# LM358.net
KiCad netlist of a schematic drawn in Altium Designer
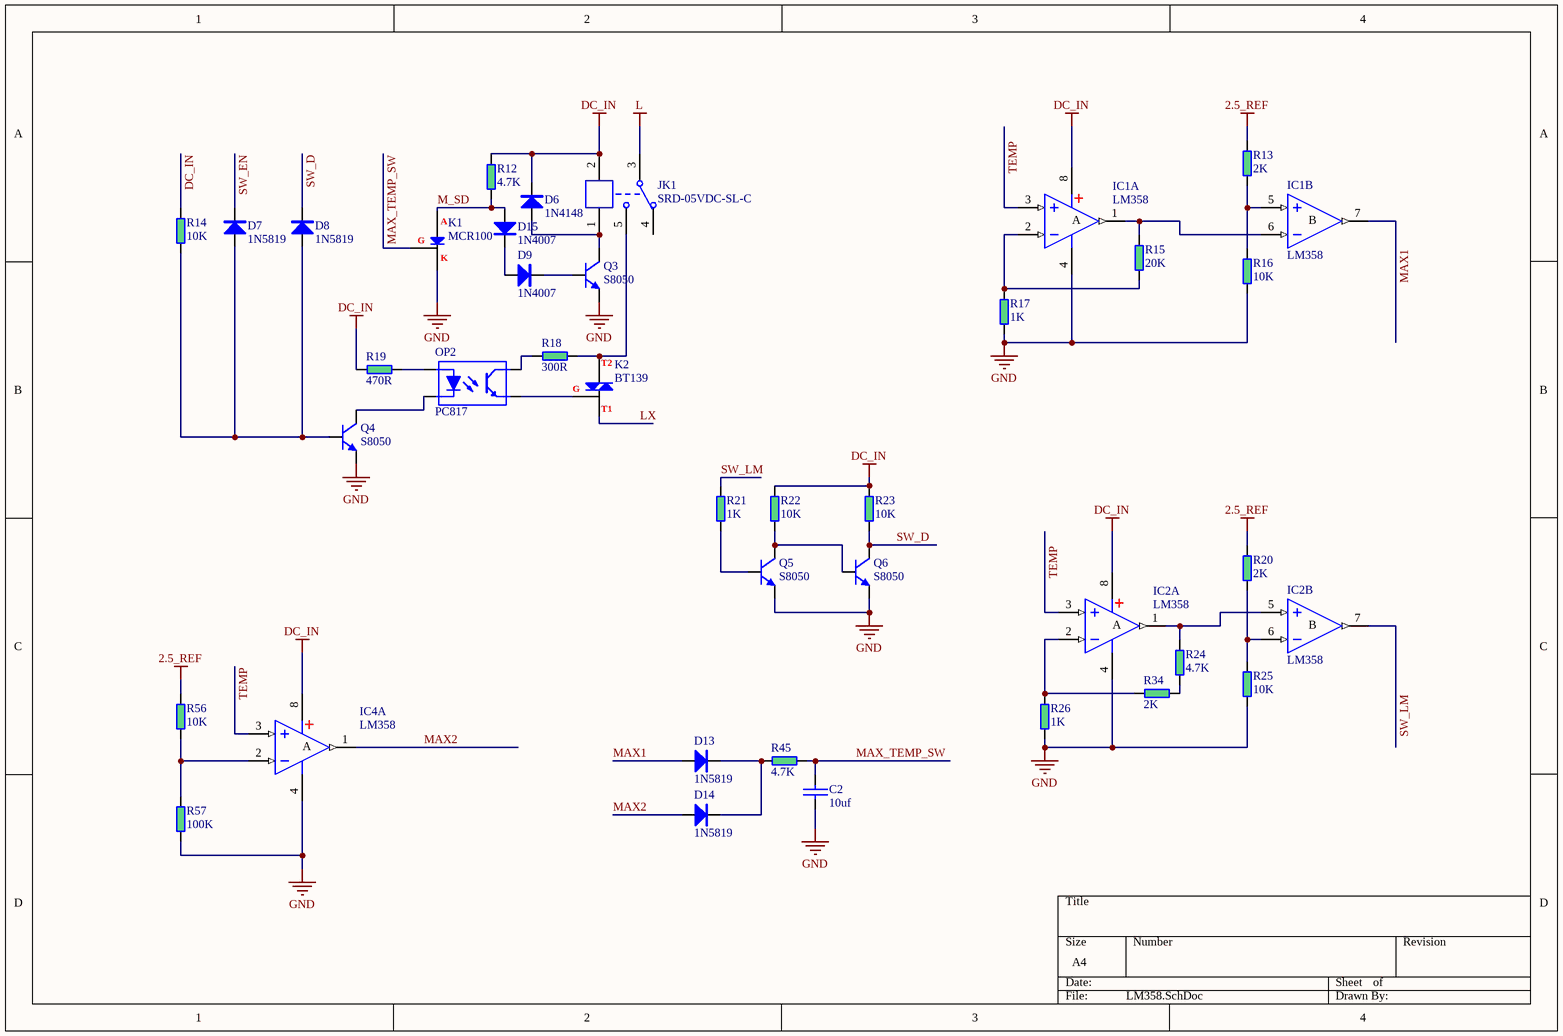
[diagram p0: LM358.SchDoc]

(export (version "E")
  (design (tool "Eeschema 10.0.6"))
  (components
    (comp (ref "C2")
      (value "10uf")
      (footprint "C 0603")
      (description "电容")
      (fields (field (name "Comment") "04.Cap"))
      (libsource (lib "电子元件") (part "04.Cap"))
    )
    (comp (ref "D6")
      (value "1N4148")
      (footprint "D 1N4148-LL34")
      (description "二极管")
      (libsource (lib "电子元件") (part "12.Diode"))
    )
    (comp (ref "D7")
      (value "1N5819")
      (footprint "D 1N5819W-SOD123")
      (description "二极管")
      (libsource (lib "电子元件") (part "12.Diode"))
    )
    (comp (ref "D8")
      (value "1N5819")
      (footprint "D 1N5819W-SOD123")
      (description "二极管")
      (libsource (lib "电子元件") (part "12.Diode"))
    )
    (comp (ref "D9")
      (value "1N4007")
      (footprint "D 1N4007-SOD123")
      (description "二极管")
      (libsource (lib "电子元件") (part "12.Diode"))
    )
    (comp (ref "D13")
      (value "1N5819")
      (footprint "D 1N5819W-SOD123")
      (description "二极管")
      (libsource (lib "电子元件") (part "12.Diode"))
    )
    (comp (ref "D14")
      (value "1N5819")
      (footprint "D 1N5819W-SOD123")
      (description "二极管")
      (libsource (lib "电子元件") (part "12.Diode"))
    )
    (comp (ref "D15")
      (value "1N4007")
      (footprint "D 1N4007-SOD123")
      (description "二极管")
      (libsource (lib "电子元件") (part "12.Diode"))
    )
    (comp (ref "IC1")
      (value "LM358")
      (footprint "SOP8")
      (description "双路运放")
      (fields (field (name "版权归属") "源创客"))
      (libsource (lib "集成IC") (part "LM358"))
    )
    (comp (ref "IC2")
      (value "LM358")
      (footprint "SOP8")
      (description "双路运放")
      (fields (field (name "版权归属") "源创客"))
      (libsource (lib "集成IC") (part "LM358"))
    )
    (comp (ref "IC4")
      (value "LM358")
      (footprint "SOP8")
      (description "双路运放")
      (fields (field (name "版权归属") "源创客"))
      (libsource (lib "集成IC") (part "LM358"))
    )
    (comp (ref "JK1")
      (value "SRD-05VDC-SL-C")
      (footprint "SRD-C_B")
      (description "5V一组转换")
      (fields (field (name "版权归属") "源创客"))
      (libsource (lib "继电器") (part "SRD-05VDC-SL-C"))
    )
    (comp (ref "K1")
      (value "MCR100")
      (footprint "IGBT MCR100-SOT23")
      (description "单向可控硅-晶闸管")
      (libsource (lib "电子元件") (part "20.IGBT"))
    )
    (comp (ref "K2")
      (value "BT139")
      (footprint "IGBT BT139")
      (description "双向可控硅-晶闸管")
      (libsource (lib "电子元件") (part "19.IGBT-Bi"))
    )
    (comp (ref "OP2")
      (value "PC817")
      (footprint "OP MOC3041")
      (description "光耦")
      (libsource (lib "电子元件") (part "17.Optocoupler"))
    )
    (comp (ref "Q3")
      (value "S8050")
      (footprint "BJT-S8050-SOT23")
      (description "三极管 NPN")
      (libsource (lib "电子元件") (part "07.BJT(N)"))
    )
    (comp (ref "Q4")
      (value "S8050")
      (footprint "BJT-S8050-SOT23")
      (description "三极管 NPN")
      (libsource (lib "电子元件") (part "07.BJT(N)"))
    )
    (comp (ref "Q5")
      (value "S8050")
      (footprint "BJT-S8050-SOT23")
      (description "三极管 NPN")
      (libsource (lib "电子元件") (part "07.BJT(N)"))
    )
    (comp (ref "Q6")
      (value "S8050")
      (footprint "BJT-S8050-SOT23")
      (description "三极管 NPN")
      (libsource (lib "电子元件") (part "07.BJT(N)"))
    )
    (comp (ref "R12")
      (value "4.7K")
      (footprint "R 0603")
      (description "电阻")
      (libsource (lib "") (part "01.Res_1"))
    )
    (comp (ref "R13")
      (value "2K")
      (footprint "R 0603")
      (description "电阻")
      (libsource (lib "") (part "01.Res_1"))
    )
    (comp (ref "R14")
      (value "10K")
      (footprint "R 0603")
      (description "电阻")
      (libsource (lib "") (part "01.Res_1"))
    )
    (comp (ref "R15")
      (value "20K")
      (footprint "R 0603")
      (description "电阻")
      (libsource (lib "") (part "01.Res_1"))
    )
    (comp (ref "R16")
      (value "10K")
      (footprint "R 0603")
      (description "电阻")
      (libsource (lib "") (part "01.Res_1"))
    )
    (comp (ref "R17")
      (value "1K")
      (footprint "R 0603")
      (description "电阻")
      (libsource (lib "") (part "01.Res_1"))
    )
    (comp (ref "R18")
      (value "300R")
      (footprint "RS 1/4W-V3")
      (description "电阻")
      (libsource (lib "电子元件") (part "01.Res"))
    )
    (comp (ref "R19")
      (value "470R")
      (footprint "R 0603")
      (description "电阻")
      (libsource (lib "电子元件") (part "01.Res"))
    )
    (comp (ref "R20")
      (value "2K")
      (footprint "R 0603")
      (description "电阻")
      (libsource (lib "") (part "01.Res_1"))
    )
    (comp (ref "R21")
      (value "1K")
      (footprint "R 0603")
      (description "电阻")
      (libsource (lib "") (part "01.Res_1"))
    )
    (comp (ref "R22")
      (value "10K")
      (footprint "R 0603")
      (description "电阻")
      (libsource (lib "") (part "01.Res_1"))
    )
    (comp (ref "R23")
      (value "10K")
      (footprint "R 0603")
      (description "电阻")
      (libsource (lib "") (part "01.Res_1"))
    )
    (comp (ref "R24")
      (value "4.7K")
      (footprint "R 0603")
      (description "电阻")
      (libsource (lib "") (part "01.Res_1"))
    )
    (comp (ref "R25")
      (value "10K")
      (footprint "R 0603")
      (description "电阻")
      (libsource (lib "") (part "01.Res_1"))
    )
    (comp (ref "R26")
      (value "1K")
      (footprint "R 0603")
      (description "电阻")
      (libsource (lib "") (part "01.Res_1"))
    )
    (comp (ref "R34")
      (value "2K")
      (footprint "R 0603")
      (description "电阻")
      (libsource (lib "电子元件") (part "01.Res"))
    )
    (comp (ref "R45")
      (value "4.7K")
      (footprint "R 0603")
      (description "电阻")
      (libsource (lib "电子元件") (part "01.Res"))
    )
    (comp (ref "R56")
      (value "10K")
      (footprint "R 0603")
      (description "电阻")
      (libsource (lib "") (part "01.Res_1"))
    )
    (comp (ref "R57")
      (value "100K")
      (footprint "R 0603")
      (description "电阻")
      (libsource (lib "") (part "01.Res_1"))
    )
  )
  (nets
    (net (code "1") (name "/LX") (class "Default")
      (node (ref "K2") (pin "T1") (pinfunction "T1_T1") (pintype "passive"))
    )
    (net (code "2") (name "/MAX1") (class "Default")
      (node (ref "D13") (pin "A") (pinfunction "A_A") (pintype "passive"))
      (node (ref "IC1") (pin "7") (pinfunction "OUT_7") (pintype "output"))
    )
    (net (code "3") (name "/MAX2") (class "Default")
      (node (ref "D14") (pin "A") (pinfunction "A_A") (pintype "passive"))
      (node (ref "IC4") (pin "1") (pinfunction "OUT_1") (pintype "output"))
    )
    (net (code "4") (name "/MAX_TEMP_SW") (class "Default")
      (node (ref "C2") (pin "1") (pinfunction "1_1") (pintype "passive"))
      (node (ref "K1") (pin "G") (pinfunction "G_G") (pintype "passive"))
      (node (ref "R45") (pin "2") (pinfunction "2_2") (pintype "passive"))
    )
    (net (code "5") (name "/M_SD") (class "Default")
      (node (ref "D15") (pin "A") (pinfunction "A_A") (pintype "passive"))
      (node (ref "K1") (pin "A") (pinfunction "A_A") (pintype "passive"))
      (node (ref "R12") (pin "1") (pinfunction "1_1") (pintype "passive"))
    )
    (net (code "6") (name "/SW_D") (class "Default")
      (node (ref "D8") (pin "K") (pinfunction "K_K") (pintype "passive"))
      (node (ref "Q6") (pin "C") (pinfunction "C_C") (pintype "passive"))
      (node (ref "R23") (pin "1") (pinfunction "1_1") (pintype "passive"))
    )
    (net (code "7") (name "/SW_EN") (class "Default")
      (node (ref "D7") (pin "K") (pinfunction "K_K") (pintype "passive"))
    )
    (net (code "8") (name "/SW_LM") (class "Default")
      (node (ref "IC2") (pin "7") (pinfunction "OUT_7") (pintype "output"))
      (node (ref "R21") (pin "2") (pinfunction "2_2") (pintype "passive"))
    )
    (net (code "9") (name "/TEMP") (class "Default")
      (node (ref "IC1") (pin "3") (pinfunction "IN+_3") (pintype "input"))
      (node (ref "IC2") (pin "3") (pinfunction "IN+_3") (pintype "input"))
      (node (ref "IC4") (pin "3") (pinfunction "IN+_3") (pintype "input"))
    )
    (net (code "10") (name "2.5_REF") (class "Default")
      (node (ref "R13") (pin "2") (pinfunction "2_2") (pintype "passive"))
      (node (ref "R20") (pin "2") (pinfunction "2_2") (pintype "passive"))
      (node (ref "R56") (pin "2") (pinfunction "2_2") (pintype "passive"))
    )
    (net (code "11") (name "DC_IN") (class "Default")
      (node (ref "D6") (pin "K") (pinfunction "K_K") (pintype "passive"))
      (node (ref "IC1") (pin "8") (pinfunction "V+_8") (pintype "power_in"))
      (node (ref "IC2") (pin "8") (pinfunction "V+_8") (pintype "power_in"))
      (node (ref "IC4") (pin "8") (pinfunction "V+_8") (pintype "power_in"))
      (node (ref "JK1") (pin "2") (pinfunction "2_2") (pintype "passive"))
      (node (ref "R12") (pin "2") (pinfunction "2_2") (pintype "passive"))
      (node (ref "R14") (pin "2") (pinfunction "2_2") (pintype "passive"))
      (node (ref "R19") (pin "1") (pinfunction "1_1") (pintype "passive"))
      (node (ref "R22") (pin "2") (pinfunction "2_2") (pintype "passive"))
      (node (ref "R23") (pin "2") (pinfunction "2_2") (pintype "passive"))
    )
    (net (code "12") (name "GND") (class "Default")
      (node (ref "C2") (pin "2") (pinfunction "2_2") (pintype "passive"))
      (node (ref "IC1") (pin "4") (pinfunction "V-_4") (pintype "power_in"))
      (node (ref "IC2") (pin "4") (pinfunction "V-_4") (pintype "power_in"))
      (node (ref "IC4") (pin "4") (pinfunction "V-_4") (pintype "power_in"))
      (node (ref "K1") (pin "K") (pinfunction "K_K") (pintype "passive"))
      (node (ref "Q3") (pin "E") (pinfunction "E_E") (pintype "passive"))
      (node (ref "Q4") (pin "E") (pinfunction "E_E") (pintype "passive"))
      (node (ref "Q5") (pin "E") (pinfunction "E_E") (pintype "passive"))
      (node (ref "Q6") (pin "E") (pinfunction "E_E") (pintype "passive"))
      (node (ref "R16") (pin "1") (pinfunction "1_1") (pintype "passive"))
      (node (ref "R17") (pin "1") (pinfunction "1_1") (pintype "passive"))
      (node (ref "R25") (pin "1") (pinfunction "1_1") (pintype "passive"))
      (node (ref "R26") (pin "1") (pinfunction "1_1") (pintype "passive"))
      (node (ref "R57") (pin "1") (pinfunction "1_1") (pintype "passive"))
    )
    (net (code "13") (name "L") (class "Default")
      (node (ref "JK1") (pin "3") (pinfunction "3_3") (pintype "passive"))
    )
    (net (code "14") (name "Net-(D6-PadA)") (class "Default")
      (node (ref "D6") (pin "A") (pinfunction "A_A") (pintype "passive"))
      (node (ref "JK1") (pin "1") (pinfunction "1_1") (pintype "passive"))
      (node (ref "Q3") (pin "C") (pinfunction "C_C") (pintype "passive"))
    )
    (net (code "15") (name "Net-(D7-PadA)") (class "Default")
      (node (ref "D7") (pin "A") (pinfunction "A_A") (pintype "passive"))
      (node (ref "D8") (pin "A") (pinfunction "A_A") (pintype "passive"))
      (node (ref "Q4") (pin "B") (pinfunction "B_B") (pintype "passive"))
      (node (ref "R14") (pin "1") (pinfunction "1_1") (pintype "passive"))
    )
    (net (code "16") (name "Net-(D9-PadK)") (class "Default")
      (node (ref "D9") (pin "K") (pinfunction "K_K") (pintype "passive"))
      (node (ref "Q3") (pin "B") (pinfunction "B_B") (pintype "passive"))
    )
    (net (code "17") (name "Net-(D13-PadK)") (class "Default")
      (node (ref "D13") (pin "K") (pinfunction "K_K") (pintype "passive"))
      (node (ref "D14") (pin "K") (pinfunction "K_K") (pintype "passive"))
      (node (ref "R45") (pin "1") (pinfunction "1_1") (pintype "passive"))
    )
    (net (code "18") (name "Net-(D15-PadK)") (class "Default")
      (node (ref "D15") (pin "K") (pinfunction "K_K") (pintype "passive"))
      (node (ref "D9") (pin "A") (pinfunction "A_A") (pintype "passive"))
    )
    (net (code "19") (name "Net-(IC1A-IN-)") (class "Default")
      (node (ref "IC1") (pin "2") (pinfunction "IN-_2") (pintype "input"))
      (node (ref "R15") (pin "1") (pinfunction "1_1") (pintype "passive"))
      (node (ref "R17") (pin "2") (pinfunction "2_2") (pintype "passive"))
    )
    (net (code "20") (name "Net-(IC1A-OUT)") (class "Default")
      (node (ref "IC1") (pin "1") (pinfunction "OUT_1") (pintype "output"))
      (node (ref "IC1") (pin "6") (pinfunction "IN-_6") (pintype "input"))
      (node (ref "R15") (pin "2") (pinfunction "2_2") (pintype "passive"))
    )
    (net (code "21") (name "Net-(IC1B-IN+)") (class "Default")
      (node (ref "IC1") (pin "5") (pinfunction "IN+_5") (pintype "input"))
      (node (ref "R13") (pin "1") (pinfunction "1_1") (pintype "passive"))
      (node (ref "R16") (pin "2") (pinfunction "2_2") (pintype "passive"))
    )
    (net (code "22") (name "Net-(IC2A-IN-)") (class "Default")
      (node (ref "IC2") (pin "2") (pinfunction "IN-_2") (pintype "input"))
      (node (ref "R26") (pin "2") (pinfunction "2_2") (pintype "passive"))
      (node (ref "R34") (pin "1") (pinfunction "1_1") (pintype "passive"))
    )
    (net (code "23") (name "Net-(IC2A-OUT)") (class "Default")
      (node (ref "IC2") (pin "1") (pinfunction "OUT_1") (pintype "output"))
      (node (ref "IC2") (pin "5") (pinfunction "IN+_5") (pintype "input"))
      (node (ref "R24") (pin "2") (pinfunction "2_2") (pintype "passive"))
    )
    (net (code "24") (name "Net-(IC2B-IN-)") (class "Default")
      (node (ref "IC2") (pin "6") (pinfunction "IN-_6") (pintype "input"))
      (node (ref "R20") (pin "1") (pinfunction "1_1") (pintype "passive"))
      (node (ref "R25") (pin "2") (pinfunction "2_2") (pintype "passive"))
    )
    (net (code "25") (name "Net-(IC4A-IN-)") (class "Default")
      (node (ref "IC4") (pin "2") (pinfunction "IN-_2") (pintype "input"))
      (node (ref "R56") (pin "1") (pinfunction "1_1") (pintype "passive"))
      (node (ref "R57") (pin "2") (pinfunction "2_2") (pintype "passive"))
    )
    (net (code "26") (name "Net-(JK1-Pad5)") (class "Default")
      (node (ref "JK1") (pin "5") (pinfunction "5_5") (pintype "passive"))
      (node (ref "K2") (pin "T2") (pinfunction "T2_T2") (pintype "passive"))
      (node (ref "R18") (pin "2") (pinfunction "2_2") (pintype "passive"))
    )
    (net (code "27") (name "Net-(K2-PadG)") (class "Default")
      (node (ref "K2") (pin "G") (pinfunction "G_G") (pintype "passive"))
      (node (ref "OP2") (pin "E") (pinfunction "E_E") (pintype "passive"))
    )
    (net (code "28") (name "Net-(OP2-PadA)") (class "Default")
      (node (ref "OP2") (pin "A") (pinfunction "A_A") (pintype "passive"))
      (node (ref "R19") (pin "2") (pinfunction "2_2") (pintype "passive"))
    )
    (net (code "29") (name "Net-(OP2-PadC)") (class "Default")
      (node (ref "OP2") (pin "C") (pinfunction "C_C") (pintype "passive"))
      (node (ref "R18") (pin "1") (pinfunction "1_1") (pintype "passive"))
    )
    (net (code "30") (name "Net-(OP2-PadK)") (class "Default")
      (node (ref "OP2") (pin "K") (pinfunction "K_K") (pintype "passive"))
      (node (ref "Q4") (pin "C") (pinfunction "C_C") (pintype "passive"))
    )
    (net (code "31") (name "Net-(Q5-PadB)") (class "Default")
      (node (ref "Q5") (pin "B") (pinfunction "B_B") (pintype "passive"))
      (node (ref "R21") (pin "1") (pinfunction "1_1") (pintype "passive"))
    )
    (net (code "32") (name "Net-(Q5-PadC)") (class "Default")
      (node (ref "Q5") (pin "C") (pinfunction "C_C") (pintype "passive"))
      (node (ref "Q6") (pin "B") (pinfunction "B_B") (pintype "passive"))
      (node (ref "R22") (pin "1") (pinfunction "1_1") (pintype "passive"))
    )
    (net (code "33") (name "Net-(R24-Pad1)") (class "Default")
      (node (ref "R24") (pin "1") (pinfunction "1_1") (pintype "passive"))
      (node (ref "R34") (pin "2") (pinfunction "2_2") (pintype "passive"))
    )
    (net (code "34") (name "unconnected-(JK1-Pad4)") (class "Default")
      (node (ref "JK1") (pin "4") (pinfunction "4_4") (pintype "passive"))
    )
  )
)
